# glucoschema.net
KiCad netlist of a schematic drawn in EAGLE
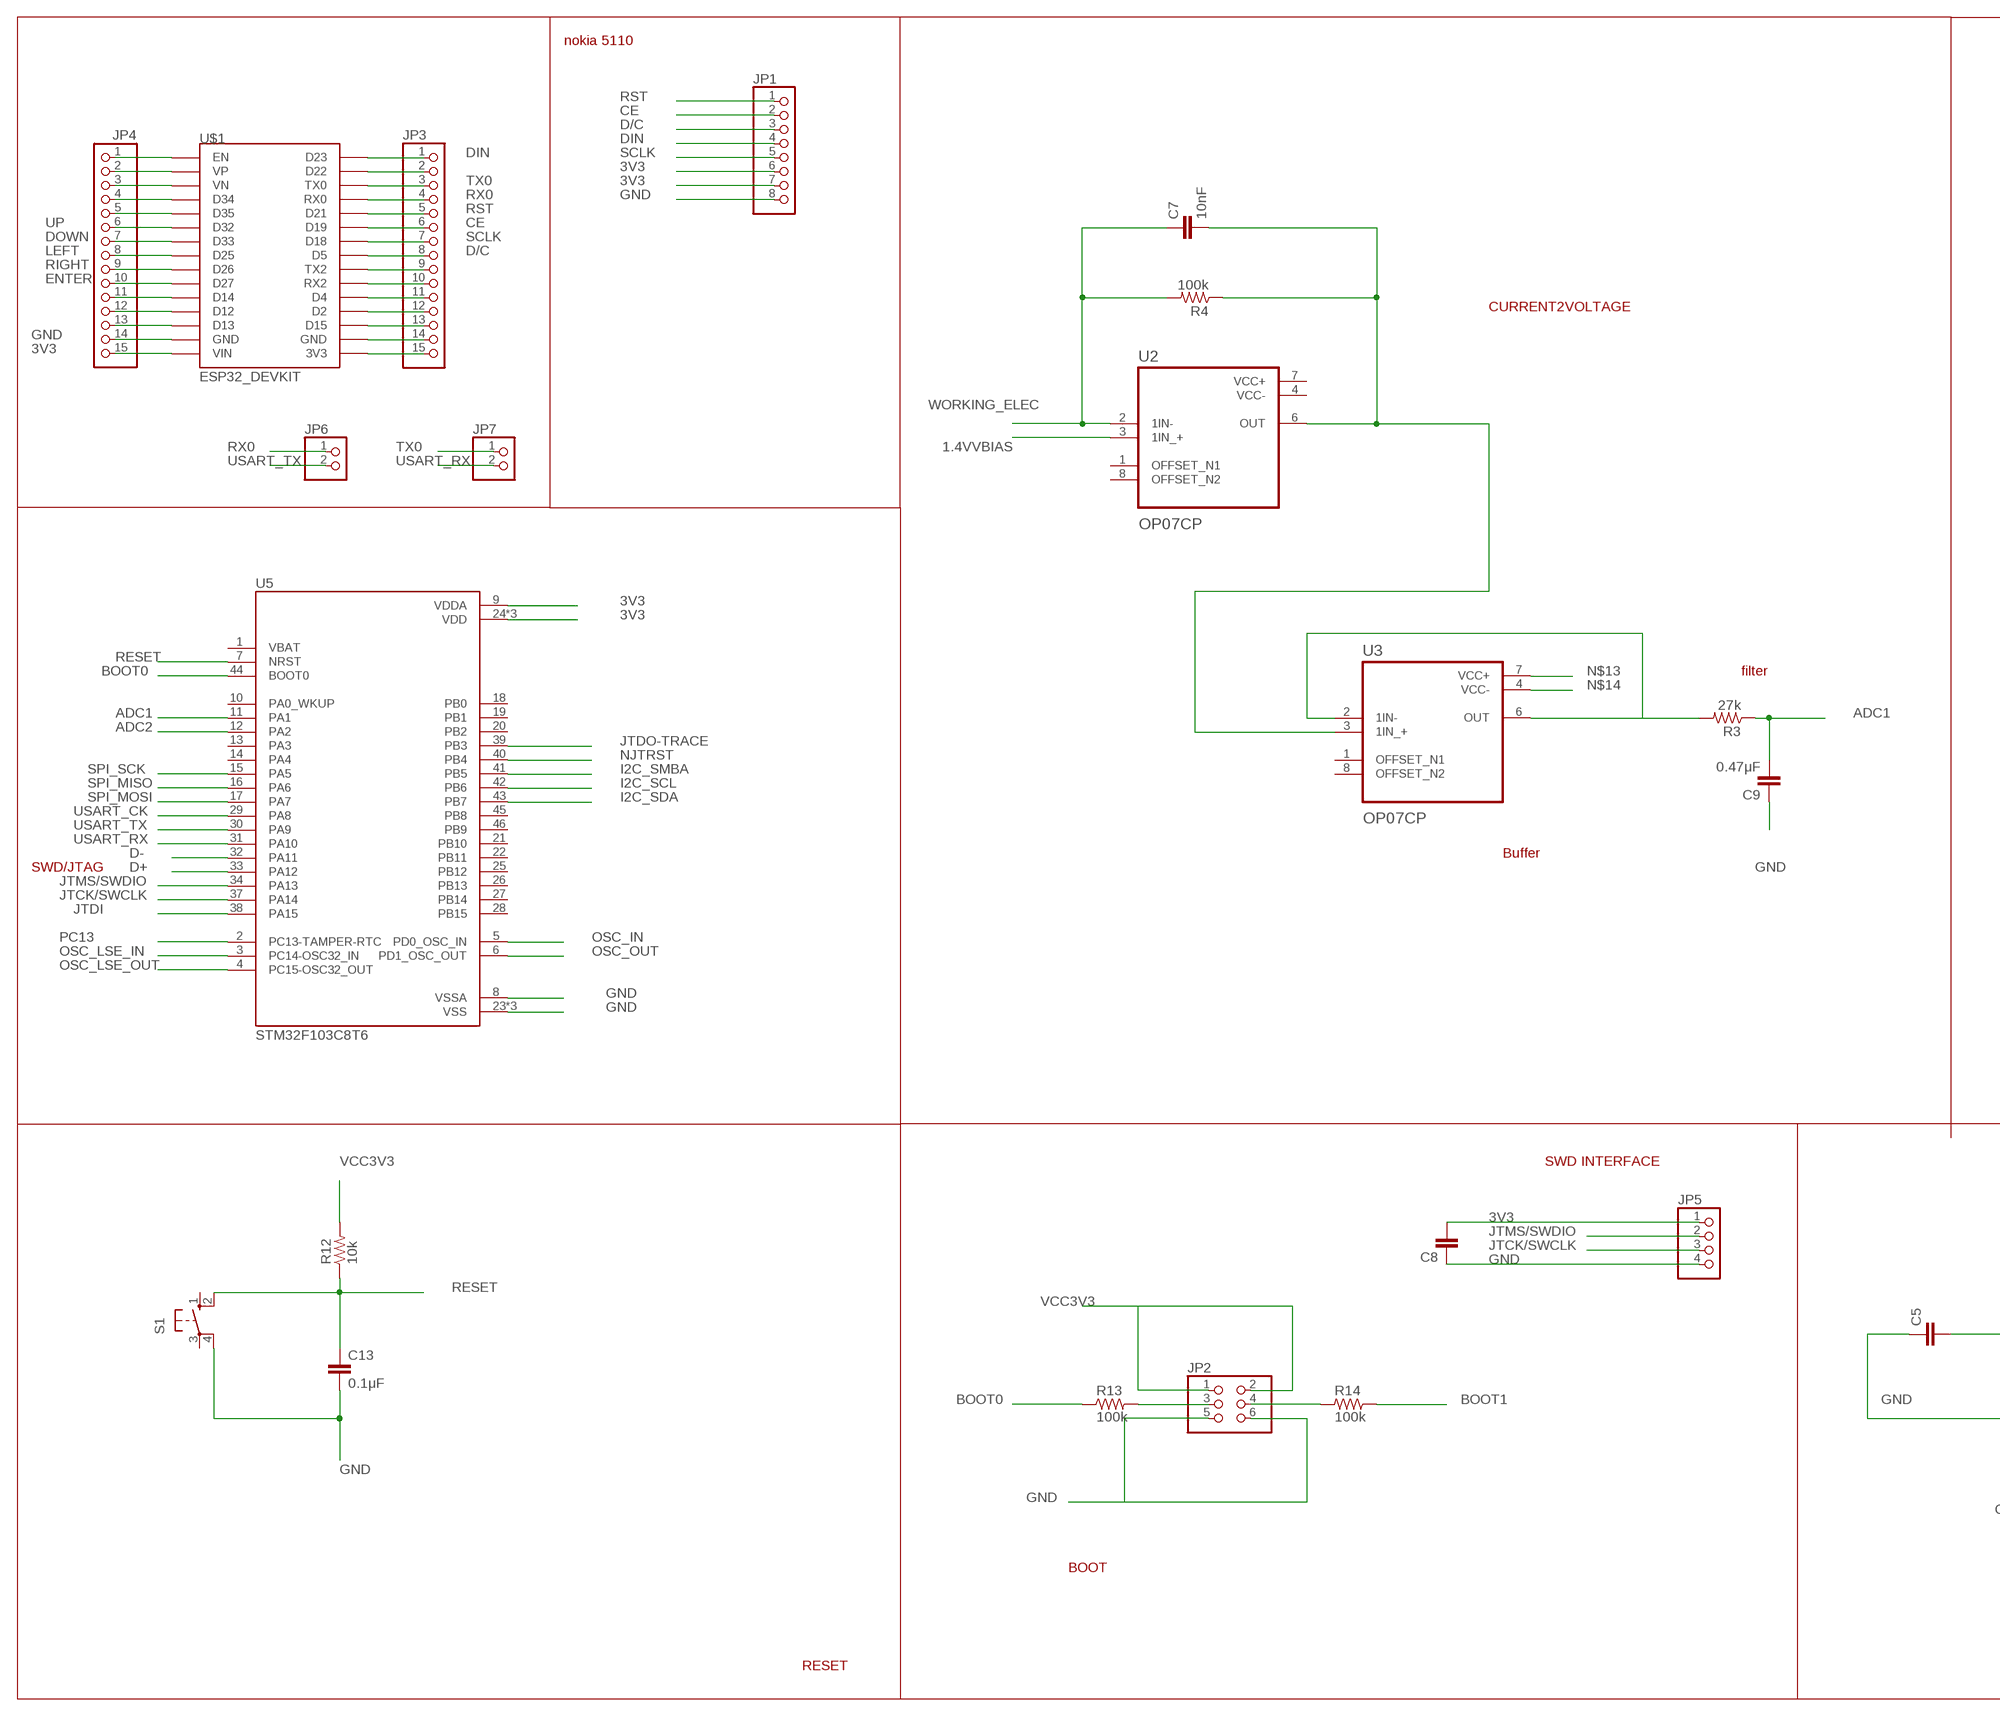
[diagram p0: schematic, sheet 1, part 1 of 2]
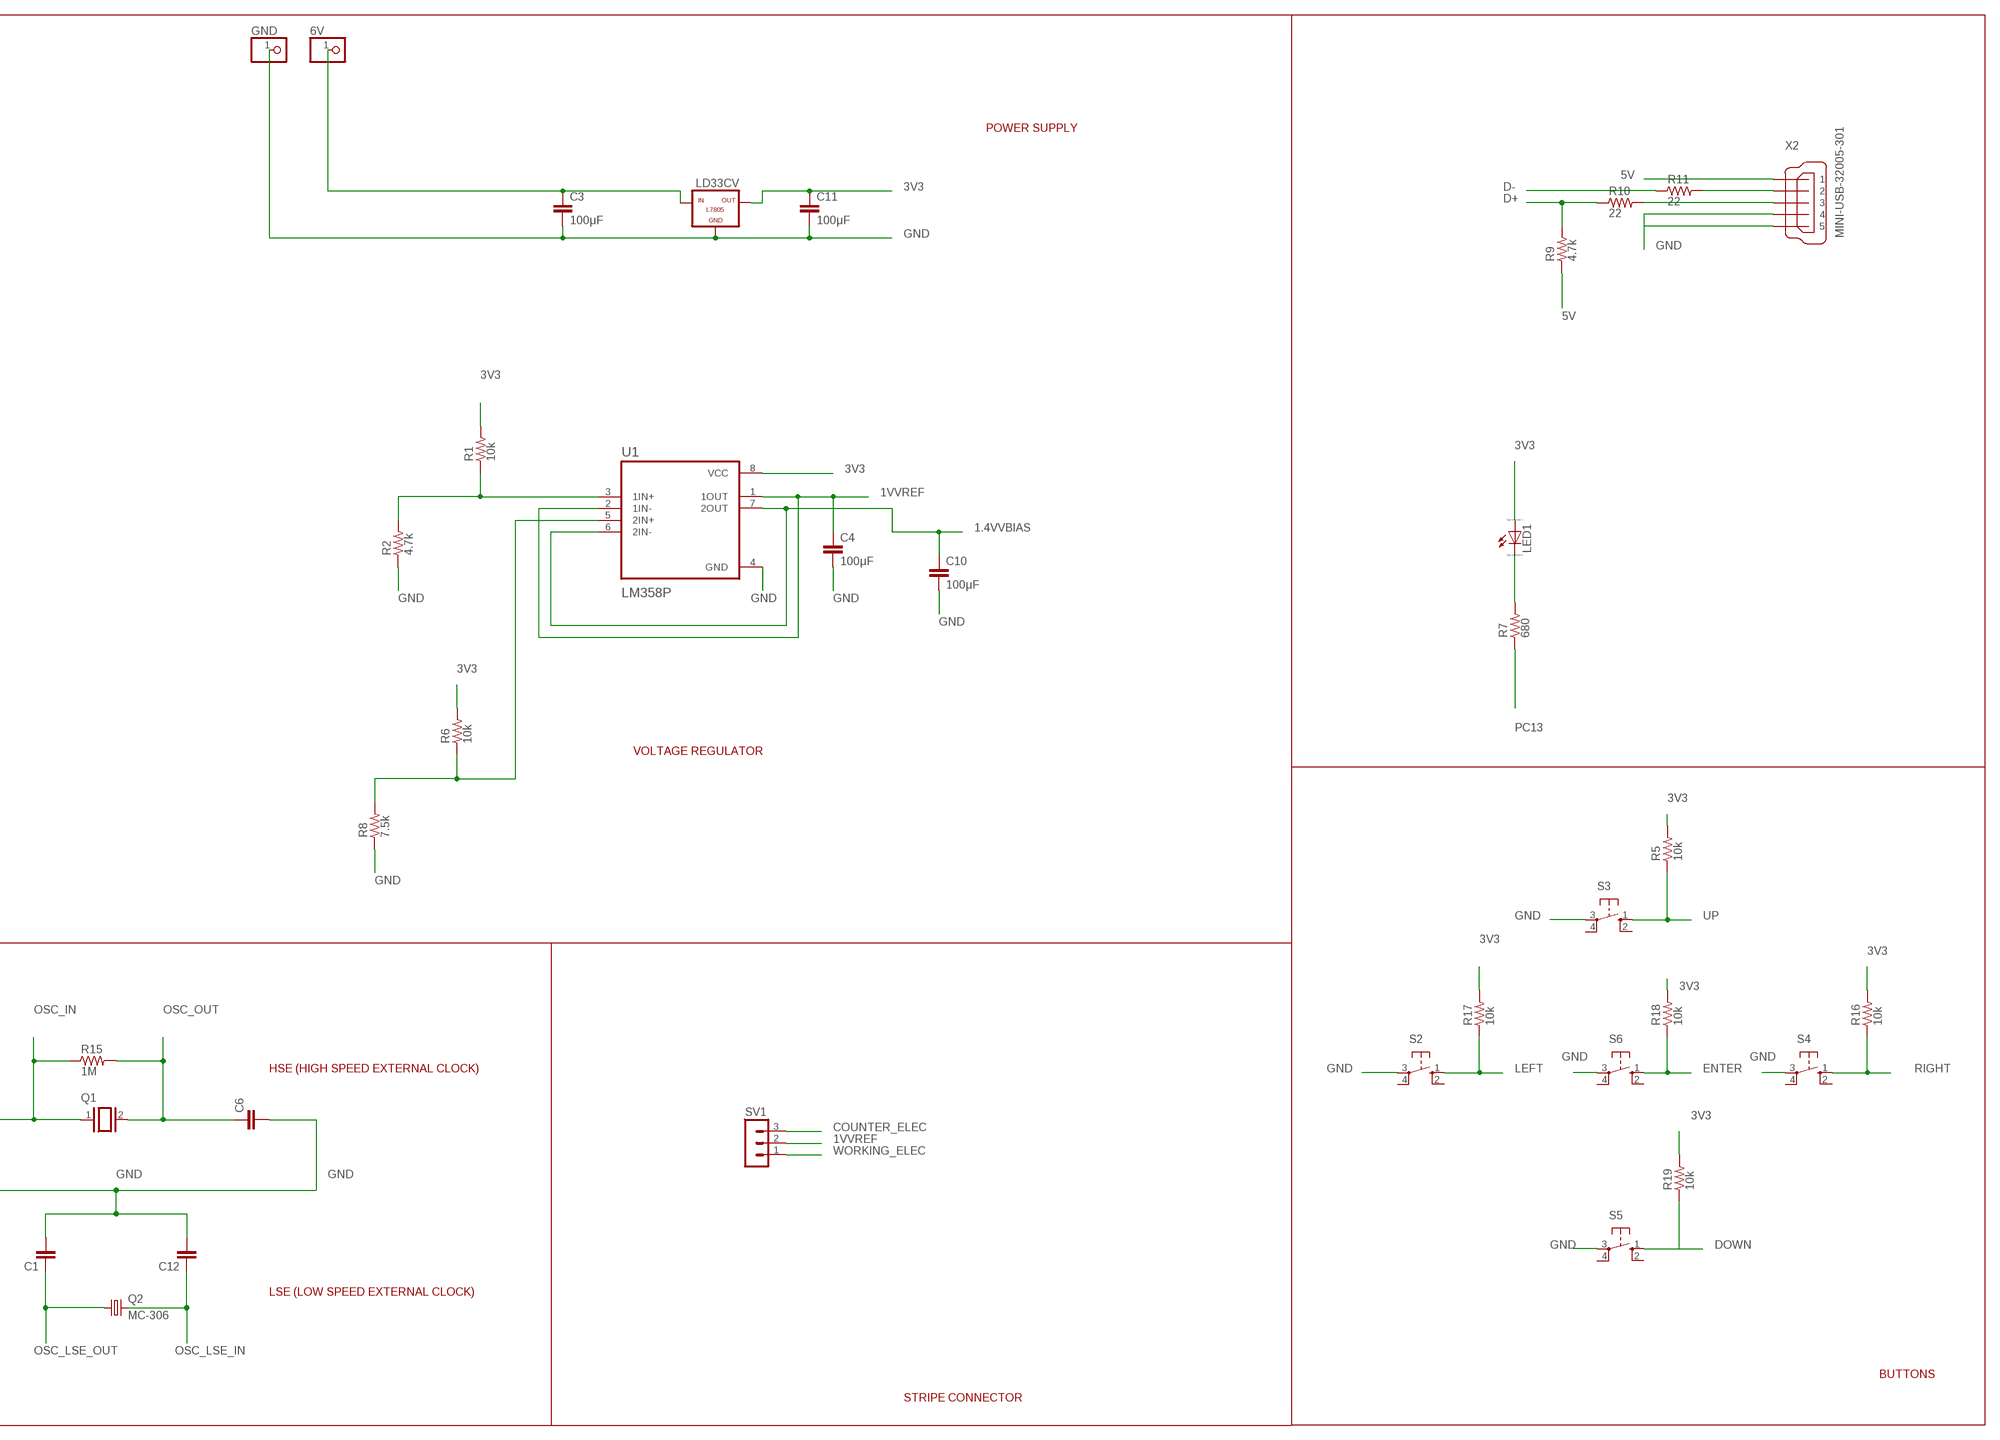
[diagram p1: schematic, sheet 1, part 2 of 2]

(export (version "E")
  (design (tool "Eeschema 10.0.6"))
  (components
    (comp (ref "6V")
      (value "PINHD-1X1")
      (footprint "eagle-import:1X01")
      (libsource (lib "eagle-import") (part "PINHD-1X1"))
    )
    (comp (ref "C1")
      (value "C2.5/4")
      (footprint "eagle-import:C2.5-4")
      (libsource (lib "eagle-import") (part "C2.5/4"))
    )
    (comp (ref "C3")
      (value "100μF")
      (footprint "eagle-import:C2.5-4")
      (libsource (lib "eagle-import") (part "C2.5/4"))
    )
    (comp (ref "C4")
      (value "100μF")
      (footprint "eagle-import:C2.5-4")
      (libsource (lib "eagle-import") (part "C2.5/4"))
    )
    (comp (ref "C5")
      (value "C2.5/4")
      (footprint "eagle-import:C2.5-4")
      (libsource (lib "eagle-import") (part "C2.5/4"))
    )
    (comp (ref "C6")
      (value "C2.5/4")
      (footprint "eagle-import:C2.5-4")
      (libsource (lib "eagle-import") (part "C2.5/4"))
    )
    (comp (ref "C7")
      (value "10nF")
      (footprint "eagle-import:C2.5-4")
      (libsource (lib "eagle-import") (part "C2.5/4"))
    )
    (comp (ref "C8")
      (value "C2.5/4")
      (footprint "eagle-import:C2.5-4")
      (libsource (lib "eagle-import") (part "C2.5/4"))
    )
    (comp (ref "C9")
      (value "0.47μF")
      (footprint "eagle-import:C2.5-4")
      (libsource (lib "eagle-import") (part "C2.5/4"))
    )
    (comp (ref "C10")
      (value "100μF")
      (footprint "eagle-import:C2.5-4")
      (libsource (lib "eagle-import") (part "C2.5/4"))
    )
    (comp (ref "C11")
      (value "100μF")
      (footprint "eagle-import:C2.5-4")
      (libsource (lib "eagle-import") (part "C2.5/4"))
    )
    (comp (ref "C12")
      (value "C2.5/4")
      (footprint "eagle-import:C2.5-4")
      (libsource (lib "eagle-import") (part "C2.5/4"))
    )
    (comp (ref "C13")
      (value "0.1μF")
      (footprint "eagle-import:C2.5-4")
      (libsource (lib "eagle-import") (part "C2.5/4"))
    )
    (comp (ref "GND")
      (value "PINHD-1X1")
      (footprint "eagle-import:1X01")
      (libsource (lib "eagle-import") (part "PINHD-1X1"))
    )
    (comp (ref "JP1")
      (value "PINHD-1X8")
      (footprint "eagle-import:1X08")
      (libsource (lib "eagle-import") (part "PINHD-1X8"))
    )
    (comp (ref "JP2")
      (value "PINHD-2X3")
      (footprint "eagle-import:2X03")
      (libsource (lib "eagle-import") (part "PINHD-2X3"))
    )
    (comp (ref "JP3")
      (value "PINHD-1X15")
      (footprint "eagle-import:1X15")
      (libsource (lib "eagle-import") (part "PINHD-1X15"))
    )
    (comp (ref "JP4")
      (value "PINHD-1X15")
      (footprint "eagle-import:1X15")
      (libsource (lib "eagle-import") (part "PINHD-1X15"))
    )
    (comp (ref "JP5")
      (value "PINHD-1X4")
      (footprint "eagle-import:1X04")
      (libsource (lib "eagle-import") (part "PINHD-1X4"))
    )
    (comp (ref "JP6")
      (value "PINHD-1X2")
      (footprint "eagle-import:1X02")
      (libsource (lib "eagle-import") (part "PINHD-1X2"))
    )
    (comp (ref "JP7")
      (value "PINHD-1X2")
      (footprint "eagle-import:1X02")
      (libsource (lib "eagle-import") (part "PINHD-1X2"))
    )
    (comp (ref "LD33CV")
      (value "-L7805")
      (footprint "eagle-import:L7805")
      (libsource (lib "eagle-import") (part "-L7805"))
    )
    (comp (ref "LED1")
      (value "LED_E")
      (footprint "eagle-import:LED_1206")
      (libsource (lib "eagle-import") (part "LED_E"))
    )
    (comp (ref "Q1")
      (value "XTAL/S")
      (footprint "eagle-import:QS")
      (libsource (lib "eagle-import") (part "XTAL/S"))
    )
    (comp (ref "Q2")
      (value "MC-306")
      (footprint "eagle-import:MC-306")
      (fields (field (name "MPN") "MC-306 60.0KHZ  100PPM ,12.5PF"))
      (libsource (lib "eagle-import") (part "MC-306"))
    )
    (comp (ref "R1")
      (value "10k")
      (footprint "eagle-import:R0805")
      (libsource (lib "eagle-import") (part "R_0805"))
    )
    (comp (ref "R2")
      (value "4.7k")
      (footprint "eagle-import:R0805")
      (libsource (lib "eagle-import") (part "R_0805"))
    )
    (comp (ref "R3")
      (value "27k")
      (footprint "eagle-import:R0805")
      (libsource (lib "eagle-import") (part "R_0805"))
    )
    (comp (ref "R4")
      (value "100k")
      (footprint "eagle-import:R0805")
      (libsource (lib "eagle-import") (part "R_0805"))
    )
    (comp (ref "R5")
      (value "10k")
      (footprint "eagle-import:R0805")
      (libsource (lib "eagle-import") (part "R_0805"))
    )
    (comp (ref "R6")
      (value "10k")
      (footprint "eagle-import:R0805")
      (libsource (lib "eagle-import") (part "R_0805"))
    )
    (comp (ref "R7")
      (value "680")
      (footprint "eagle-import:R0805")
      (libsource (lib "eagle-import") (part "R_0805"))
    )
    (comp (ref "R8")
      (value "7.5k")
      (footprint "eagle-import:R0805")
      (libsource (lib "eagle-import") (part "R_0805"))
    )
    (comp (ref "R9")
      (value "4.7k")
      (footprint "eagle-import:R0805")
      (libsource (lib "eagle-import") (part "R_0805"))
    )
    (comp (ref "R10")
      (value "22")
      (footprint "eagle-import:R0805")
      (libsource (lib "eagle-import") (part "R_0805"))
    )
    (comp (ref "R11")
      (value "22")
      (footprint "eagle-import:R0805")
      (libsource (lib "eagle-import") (part "R_0805"))
    )
    (comp (ref "R12")
      (value "10k")
      (footprint "eagle-import:R0805")
      (libsource (lib "eagle-import") (part "R_0805"))
    )
    (comp (ref "R13")
      (value "100k")
      (footprint "eagle-import:R0805")
      (libsource (lib "eagle-import") (part "R_0805"))
    )
    (comp (ref "R14")
      (value "100k")
      (footprint "eagle-import:R0805")
      (libsource (lib "eagle-import") (part "R_0805"))
    )
    (comp (ref "R15")
      (value "1M")
      (footprint "eagle-import:R0805")
      (libsource (lib "eagle-import") (part "R_0805"))
    )
    (comp (ref "R16")
      (value "10k")
      (footprint "eagle-import:R0805")
      (libsource (lib "eagle-import") (part "R_0805"))
    )
    (comp (ref "R17")
      (value "10k")
      (footprint "eagle-import:R0805")
      (libsource (lib "eagle-import") (part "R_0805"))
    )
    (comp (ref "R18")
      (value "10k")
      (footprint "eagle-import:R0805")
      (libsource (lib "eagle-import") (part "R_0805"))
    )
    (comp (ref "R19")
      (value "10k")
      (footprint "eagle-import:R0805")
      (libsource (lib "eagle-import") (part "R_0805"))
    )
    (comp (ref "S1")
      (value "10-XX")
      (footprint "eagle-import:B3F-10XX")
      (fields (field (name "MPN") "B3F-1000"))
      (libsource (lib "eagle-import") (part "10-XX"))
    )
    (comp (ref "S2")
      (value "10-XX")
      (footprint "eagle-import:B3F-10XX")
      (fields (field (name "MPN") "B3F-1000"))
      (libsource (lib "eagle-import") (part "10-XX"))
    )
    (comp (ref "S3")
      (value "10-XX")
      (footprint "eagle-import:B3F-10XX")
      (fields (field (name "MPN") "B3F-1000"))
      (libsource (lib "eagle-import") (part "10-XX"))
    )
    (comp (ref "S4")
      (value "10-XX")
      (footprint "eagle-import:B3F-10XX")
      (fields (field (name "MPN") "B3F-1000"))
      (libsource (lib "eagle-import") (part "10-XX"))
    )
    (comp (ref "S5")
      (value "10-XX")
      (footprint "eagle-import:B3F-10XX")
      (fields (field (name "MPN") "B3F-1000"))
      (libsource (lib "eagle-import") (part "10-XX"))
    )
    (comp (ref "S6")
      (value "10-XX")
      (footprint "eagle-import:B3F-10XX")
      (fields (field (name "MPN") "B3F-1000"))
      (libsource (lib "eagle-import") (part "10-XX"))
    )
    (comp (ref "SV1")
      (value "MA03-1")
      (footprint "eagle-import:MA03-1")
      (libsource (lib "eagle-import") (part "MA03-1"))
    )
    (comp (ref "U$1")
      (value "ESP32_DEVKIT")
      (footprint "eagle-import:ESP32_DEVKIT")
      (libsource (lib "eagle-import") (part "ESP32_DEVKIT"))
    )
    (comp (ref "U1")
      (value "LM358P")
      (footprint "eagle-import:DIP794W45P254L959H508Q8")
      (fields (field (name "MF") "Texas Instruments"))
      (libsource (lib "eagle-import") (part "LM358P"))
    )
    (comp (ref "U2")
      (value "OP07CP")
      (footprint "eagle-import:DIP794W45P254L959H508Q8")
      (fields (field (name "MF") "Texas Instruments"))
      (libsource (lib "eagle-import") (part "OP07CP"))
    )
    (comp (ref "U3")
      (value "OP07CP")
      (footprint "eagle-import:DIP794W45P254L959H508Q8")
      (fields (field (name "MF") "Texas Instruments"))
      (libsource (lib "eagle-import") (part "OP07CP"))
    )
    (comp (ref "U5")
      (value "STM32F103C8T6")
      (footprint "eagle-import:QFP50P900X900X160-48N")
      (fields (field (name "MF") "STMicroelectronics"))
      (libsource (lib "eagle-import") (part "STM32F103C8T6"))
    )
    (comp (ref "X2")
      (value "MINI-USB-32005-301")
      (footprint "eagle-import:32005-301")
      (libsource (lib "eagle-import") (part "MINI-USB-32005-301"))
    )
  )
  (nets
    (net (code "1") (name "/1.4VVBIAS") (class "Default")
      (node (ref "C10") (pin "1") (pinfunction "1_1") (pintype "passive"))
      (node (ref "U1") (pin "6") (pinfunction "2IN-_6") (pintype "input"))
      (node (ref "U1") (pin "7") (pinfunction "2OUT_7") (pintype "output"))
      (node (ref "U2") (pin "3") (pinfunction "1IN_+_3") (pintype "input"))
    )
    (net (code "2") (name "/1VVREF") (class "Default")
      (node (ref "C4") (pin "1") (pinfunction "1_1") (pintype "passive"))
      (node (ref "SV1") (pin "2") (pinfunction "2_2") (pintype "passive"))
      (node (ref "U1") (pin "1") (pinfunction "1OUT_1") (pintype "output"))
      (node (ref "U1") (pin "2") (pinfunction "1IN-_2") (pintype "input"))
    )
    (net (code "3") (name "/3V3") (class "Default")
      (node (ref "C11") (pin "1") (pinfunction "1_1") (pintype "passive"))
      (node (ref "C8") (pin "2") (pinfunction "2_2") (pintype "passive"))
      (node (ref "JP1") (pin "6") (pinfunction "6_6") (pintype "passive"))
      (node (ref "JP1") (pin "7") (pinfunction "7_7") (pintype "passive"))
      (node (ref "JP4") (pin "15") (pinfunction "15_15") (pintype "passive"))
      (node (ref "JP5") (pin "1") (pinfunction "1_1") (pintype "passive"))
      (node (ref "LD33CV") (pin "OUT") (pinfunction "OUT_OUT") (pintype "passive"))
      (node (ref "LED1") (pin "A") (pinfunction "A_A") (pintype "passive"))
      (node (ref "R1") (pin "2") (pinfunction "2_2") (pintype "passive"))
      (node (ref "R16") (pin "2") (pinfunction "2_2") (pintype "passive"))
      (node (ref "R17") (pin "2") (pinfunction "2_2") (pintype "passive"))
      (node (ref "R18") (pin "2") (pinfunction "2_2") (pintype "passive"))
      (node (ref "R19") (pin "2") (pinfunction "2_2") (pintype "passive"))
      (node (ref "R5") (pin "2") (pinfunction "2_2") (pintype "passive"))
      (node (ref "R6") (pin "2") (pinfunction "2_2") (pintype "passive"))
      (node (ref "U$1") (pin "VIN") (pinfunction "VIN_VIN") (pintype "bidirectional"))
      (node (ref "U1") (pin "8") (pinfunction "VCC_8") (pintype "power_in"))
      (node (ref "U5") (pin "24") (pinfunction "VDD_24") (pintype "power_in"))
      (node (ref "U5") (pin "36") (pinfunction "VDD_36") (pintype "power_in"))
      (node (ref "U5") (pin "48") (pinfunction "VDD_48") (pintype "power_in"))
      (node (ref "U5") (pin "9") (pinfunction "VDDA_9") (pintype "power_in"))
    )
    (net (code "4") (name "/5V") (class "Default")
      (node (ref "R9") (pin "1") (pinfunction "1_1") (pintype "passive"))
      (node (ref "X2") (pin "1") (pinfunction "1_1") (pintype "passive"))
    )
    (net (code "5") (name "/ADC1") (class "Default")
      (node (ref "C9") (pin "2") (pinfunction "2_2") (pintype "passive"))
      (node (ref "R3") (pin "1") (pinfunction "1_1") (pintype "passive"))
      (node (ref "U5") (pin "11") (pinfunction "PA1_11") (pintype "bidirectional"))
    )
    (net (code "6") (name "/ADC2") (class "Default")
      (node (ref "U5") (pin "12") (pinfunction "PA2_12") (pintype "bidirectional"))
    )
    (net (code "7") (name "/BOOT0") (class "Default")
      (node (ref "R13") (pin "1") (pinfunction "1_1") (pintype "passive"))
      (node (ref "U5") (pin "44") (pinfunction "BOOT0_44") (pintype "input"))
    )
    (net (code "8") (name "/BOOT1") (class "Default")
      (node (ref "R14") (pin "2") (pinfunction "2_2") (pintype "passive"))
    )
    (net (code "9") (name "/CE") (class "Default")
      (node (ref "JP1") (pin "2") (pinfunction "2_2") (pintype "passive"))
      (node (ref "JP3") (pin "6") (pinfunction "6_6") (pintype "passive"))
      (node (ref "U$1") (pin "D19") (pinfunction "D19_D19") (pintype "bidirectional"))
    )
    (net (code "10") (name "/COUNTER_ELEC") (class "Default")
      (node (ref "SV1") (pin "3") (pinfunction "3_3") (pintype "passive"))
    )
    (net (code "11") (name "/D+") (class "Default")
      (node (ref "R10") (pin "1") (pinfunction "1_1") (pintype "passive"))
      (node (ref "R9") (pin "2") (pinfunction "2_2") (pintype "passive"))
      (node (ref "U5") (pin "33") (pinfunction "PA12_33") (pintype "bidirectional"))
    )
    (net (code "12") (name "/D-") (class "Default")
      (node (ref "R11") (pin "1") (pinfunction "1_1") (pintype "passive"))
      (node (ref "U5") (pin "32") (pinfunction "PA11_32") (pintype "bidirectional"))
    )
    (net (code "13") (name "/DIN") (class "Default")
      (node (ref "JP1") (pin "4") (pinfunction "4_4") (pintype "passive"))
      (node (ref "JP3") (pin "1") (pinfunction "1_1") (pintype "passive"))
      (node (ref "U$1") (pin "D23") (pinfunction "D23_D23") (pintype "bidirectional"))
    )
    (net (code "14") (name "/DOWN") (class "Default")
      (node (ref "JP4") (pin "7") (pinfunction "7_7") (pintype "passive"))
      (node (ref "R19") (pin "1") (pinfunction "1_1") (pintype "passive"))
      (node (ref "S5") (pin "1") (pinfunction "S_1") (pintype "passive"))
      (node (ref "U$1") (pin "D33") (pinfunction "D33_D33") (pintype "bidirectional"))
    )
    (net (code "15") (name "/D{slash}C") (class "Default")
      (node (ref "JP1") (pin "3") (pinfunction "3_3") (pintype "passive"))
      (node (ref "JP3") (pin "8") (pinfunction "8_8") (pintype "passive"))
      (node (ref "U$1") (pin "D5") (pinfunction "D5_D5") (pintype "bidirectional"))
    )
    (net (code "16") (name "/ENTER") (class "Default")
      (node (ref "JP4") (pin "10") (pinfunction "10_10") (pintype "passive"))
      (node (ref "R18") (pin "1") (pinfunction "1_1") (pintype "passive"))
      (node (ref "S6") (pin "1") (pinfunction "S_1") (pintype "passive"))
      (node (ref "U$1") (pin "D27") (pinfunction "D27_D27") (pintype "bidirectional"))
    )
    (net (code "17") (name "/GND") (class "Default")
      (node (ref "C1") (pin "2") (pinfunction "2_2") (pintype "passive"))
      (node (ref "C10") (pin "2") (pinfunction "2_2") (pintype "passive"))
      (node (ref "C11") (pin "2") (pinfunction "2_2") (pintype "passive"))
      (node (ref "C12") (pin "2") (pinfunction "2_2") (pintype "passive"))
      (node (ref "C13") (pin "2") (pinfunction "2_2") (pintype "passive"))
      (node (ref "C3") (pin "2") (pinfunction "2_2") (pintype "passive"))
      (node (ref "C4") (pin "2") (pinfunction "2_2") (pintype "passive"))
      (node (ref "C5") (pin "1") (pinfunction "1_1") (pintype "passive"))
      (node (ref "C6") (pin "2") (pinfunction "2_2") (pintype "passive"))
      (node (ref "C8") (pin "1") (pinfunction "1_1") (pintype "passive"))
      (node (ref "C9") (pin "1") (pinfunction "1_1") (pintype "passive"))
      (node (ref "GND") (pin "1") (pinfunction "1_1") (pintype "passive"))
      (node (ref "JP1") (pin "8") (pinfunction "8_8") (pintype "passive"))
      (node (ref "JP2") (pin "6") (pinfunction "6_6") (pintype "passive"))
      (node (ref "JP4") (pin "14") (pinfunction "14_14") (pintype "passive"))
      (node (ref "JP5") (pin "4") (pinfunction "4_4") (pintype "passive"))
      (node (ref "LD33CV") (pin "GND") (pinfunction "GND_GND") (pintype "input"))
      (node (ref "R2") (pin "1") (pinfunction "1_1") (pintype "passive"))
      (node (ref "R8") (pin "1") (pinfunction "1_1") (pintype "passive"))
      (node (ref "S1") (pin "4") (pinfunction "P1_4") (pintype "passive"))
      (node (ref "S2") (pin "3") (pinfunction "P_3") (pintype "passive"))
      (node (ref "S3") (pin "3") (pinfunction "P_3") (pintype "passive"))
      (node (ref "S4") (pin "3") (pinfunction "P_3") (pintype "passive"))
      (node (ref "S5") (pin "3") (pinfunction "P_3") (pintype "passive"))
      (node (ref "S6") (pin "3") (pinfunction "P_3") (pintype "passive"))
      (node (ref "U$1") (pin "GND@1") (pinfunction "GND_GND@1") (pintype "bidirectional"))
      (node (ref "U1") (pin "4") (pinfunction "GND_4") (pintype "power_in"))
      (node (ref "U5") (pin "23") (pinfunction "VSS_23") (pintype "power_in"))
      (node (ref "U5") (pin "35") (pinfunction "VSS_35") (pintype "power_in"))
      (node (ref "U5") (pin "47") (pinfunction "VSS_47") (pintype "power_in"))
      (node (ref "U5") (pin "8") (pinfunction "VSSA_8") (pintype "power_in"))
      (node (ref "X2") (pin "4") (pinfunction "4_4") (pintype "passive"))
    )
    (net (code "18") (name "/I2C_SCL") (class "Default")
      (node (ref "U5") (pin "42") (pinfunction "PB6_42") (pintype "bidirectional"))
    )
    (net (code "19") (name "/I2C_SDA") (class "Default")
      (node (ref "U5") (pin "43") (pinfunction "PB7_43") (pintype "bidirectional"))
    )
    (net (code "20") (name "/I2C_SMBA") (class "Default")
      (node (ref "U5") (pin "41") (pinfunction "PB5_41") (pintype "bidirectional"))
    )
    (net (code "21") (name "/JTCK{slash}SWCLK") (class "Default")
      (node (ref "JP5") (pin "3") (pinfunction "3_3") (pintype "passive"))
      (node (ref "U5") (pin "37") (pinfunction "PA14_37") (pintype "bidirectional"))
    )
    (net (code "22") (name "/JTDI") (class "Default")
      (node (ref "U5") (pin "38") (pinfunction "PA15_38") (pintype "bidirectional"))
    )
    (net (code "23") (name "/JTDO-TRACE") (class "Default")
      (node (ref "U5") (pin "39") (pinfunction "PB3_39") (pintype "bidirectional"))
    )
    (net (code "24") (name "/JTMS{slash}SWDIO") (class "Default")
      (node (ref "JP5") (pin "2") (pinfunction "2_2") (pintype "passive"))
      (node (ref "U5") (pin "34") (pinfunction "PA13_34") (pintype "bidirectional"))
    )
    (net (code "25") (name "/LEFT") (class "Default")
      (node (ref "JP4") (pin "8") (pinfunction "8_8") (pintype "passive"))
      (node (ref "R17") (pin "1") (pinfunction "1_1") (pintype "passive"))
      (node (ref "S2") (pin "1") (pinfunction "S_1") (pintype "passive"))
      (node (ref "U$1") (pin "D25") (pinfunction "D25_D25") (pintype "bidirectional"))
    )
    (net (code "26") (name "/N$13") (class "Default")
      (node (ref "U3") (pin "7") (pinfunction "VCC+_7") (pintype "power_in"))
    )
    (net (code "27") (name "/N$14") (class "Default")
      (node (ref "U3") (pin "4") (pinfunction "VCC-_4") (pintype "power_in"))
    )
    (net (code "28") (name "/NJTRST") (class "Default")
      (node (ref "U5") (pin "40") (pinfunction "PB4_40") (pintype "bidirectional"))
    )
    (net (code "29") (name "/OSC_IN") (class "Default")
      (node (ref "C5") (pin "2") (pinfunction "2_2") (pintype "passive"))
      (node (ref "Q1") (pin "1") (pinfunction "1_1") (pintype "passive"))
      (node (ref "R15") (pin "1") (pinfunction "1_1") (pintype "passive"))
      (node (ref "U5") (pin "5") (pinfunction "PD0_OSC_IN_5") (pintype "bidirectional"))
    )
    (net (code "30") (name "/OSC_LSE_IN") (class "Default")
      (node (ref "C12") (pin "1") (pinfunction "1_1") (pintype "passive"))
      (node (ref "Q2") (pin "4") (pinfunction "2_4") (pintype "passive"))
      (node (ref "U5") (pin "3") (pinfunction "PC14-OSC32_IN_3") (pintype "bidirectional"))
    )
    (net (code "31") (name "/OSC_LSE_OUT") (class "Default")
      (node (ref "C1") (pin "1") (pinfunction "1_1") (pintype "passive"))
      (node (ref "Q2") (pin "1") (pinfunction "1_1") (pintype "passive"))
      (node (ref "U5") (pin "4") (pinfunction "PC15-OSC32_OUT_4") (pintype "bidirectional"))
    )
    (net (code "32") (name "/OSC_OUT") (class "Default")
      (node (ref "C6") (pin "1") (pinfunction "1_1") (pintype "passive"))
      (node (ref "Q1") (pin "2") (pinfunction "2_2") (pintype "passive"))
      (node (ref "R15") (pin "2") (pinfunction "2_2") (pintype "passive"))
      (node (ref "U5") (pin "6") (pinfunction "PD1_OSC_OUT_6") (pintype "bidirectional"))
    )
    (net (code "33") (name "/PC13") (class "Default")
      (node (ref "R7") (pin "1") (pinfunction "1_1") (pintype "passive"))
      (node (ref "U5") (pin "2") (pinfunction "PC13-TAMPER-RTC_2") (pintype "bidirectional"))
    )
    (net (code "34") (name "/RESET") (class "Default")
      (node (ref "C13") (pin "1") (pinfunction "1_1") (pintype "passive"))
      (node (ref "R12") (pin "1") (pinfunction "1_1") (pintype "passive"))
      (node (ref "S1") (pin "2") (pinfunction "S1_2") (pintype "passive"))
      (node (ref "U5") (pin "7") (pinfunction "NRST_7") (pintype "input"))
    )
    (net (code "35") (name "/RIGHT") (class "Default")
      (node (ref "JP4") (pin "9") (pinfunction "9_9") (pintype "passive"))
      (node (ref "R16") (pin "1") (pinfunction "1_1") (pintype "passive"))
      (node (ref "S4") (pin "1") (pinfunction "S_1") (pintype "passive"))
      (node (ref "U$1") (pin "D26") (pinfunction "D26_D26") (pintype "bidirectional"))
    )
    (net (code "36") (name "/RST") (class "Default")
      (node (ref "JP1") (pin "1") (pinfunction "1_1") (pintype "passive"))
      (node (ref "JP3") (pin "5") (pinfunction "5_5") (pintype "passive"))
      (node (ref "U$1") (pin "D21") (pinfunction "D21_D21") (pintype "bidirectional"))
    )
    (net (code "37") (name "/RX0") (class "Default")
      (node (ref "JP3") (pin "4") (pinfunction "4_4") (pintype "passive"))
      (node (ref "JP6") (pin "1") (pinfunction "1_1") (pintype "passive"))
      (node (ref "U$1") (pin "RX0") (pinfunction "RX0_RX0") (pintype "bidirectional"))
    )
    (net (code "38") (name "/SCLK") (class "Default")
      (node (ref "JP1") (pin "5") (pinfunction "5_5") (pintype "passive"))
      (node (ref "JP3") (pin "7") (pinfunction "7_7") (pintype "passive"))
      (node (ref "U$1") (pin "D18") (pinfunction "D18_D18") (pintype "bidirectional"))
    )
    (net (code "39") (name "/SPI_MISO") (class "Default")
      (node (ref "U5") (pin "16") (pinfunction "PA6_16") (pintype "bidirectional"))
    )
    (net (code "40") (name "/SPI_MOSI") (class "Default")
      (node (ref "U5") (pin "17") (pinfunction "PA7_17") (pintype "bidirectional"))
    )
    (net (code "41") (name "/SPI_SCK") (class "Default")
      (node (ref "U5") (pin "15") (pinfunction "PA5_15") (pintype "bidirectional"))
    )
    (net (code "42") (name "/TX0") (class "Default")
      (node (ref "JP3") (pin "3") (pinfunction "3_3") (pintype "passive"))
      (node (ref "JP7") (pin "1") (pinfunction "1_1") (pintype "passive"))
      (node (ref "U$1") (pin "TX0") (pinfunction "TX0_TX0") (pintype "bidirectional"))
    )
    (net (code "43") (name "/UP") (class "Default")
      (node (ref "JP4") (pin "6") (pinfunction "6_6") (pintype "passive"))
      (node (ref "R5") (pin "1") (pinfunction "1_1") (pintype "passive"))
      (node (ref "S3") (pin "1") (pinfunction "S_1") (pintype "passive"))
      (node (ref "U$1") (pin "D32") (pinfunction "D32_D32") (pintype "bidirectional"))
    )
    (net (code "44") (name "/USART_CK") (class "Default")
      (node (ref "U5") (pin "29") (pinfunction "PA8_29") (pintype "bidirectional"))
    )
    (net (code "45") (name "/USART_RX") (class "Default")
      (node (ref "JP7") (pin "2") (pinfunction "2_2") (pintype "passive"))
      (node (ref "U5") (pin "31") (pinfunction "PA10_31") (pintype "bidirectional"))
    )
    (net (code "46") (name "/USART_TX") (class "Default")
      (node (ref "JP6") (pin "2") (pinfunction "2_2") (pintype "passive"))
      (node (ref "U5") (pin "30") (pinfunction "PA9_30") (pintype "bidirectional"))
    )
    (net (code "47") (name "/VCC+") (class "Default")
      (node (ref "U2") (pin "7") (pinfunction "VCC+_7") (pintype "power_in"))
    )
    (net (code "48") (name "/VCC-") (class "Default")
      (node (ref "U2") (pin "4") (pinfunction "VCC-_4") (pintype "power_in"))
    )
    (net (code "49") (name "/VCC3V3") (class "Default")
      (node (ref "JP2") (pin "2") (pinfunction "2_2") (pintype "passive"))
      (node (ref "R12") (pin "2") (pinfunction "2_2") (pintype "passive"))
    )
    (net (code "50") (name "/WORKING_ELEC") (class "Default")
      (node (ref "C7") (pin "1") (pinfunction "1_1") (pintype "passive"))
      (node (ref "R4") (pin "2") (pinfunction "2_2") (pintype "passive"))
      (node (ref "SV1") (pin "1") (pinfunction "1_1") (pintype "passive"))
      (node (ref "U2") (pin "2") (pinfunction "1IN-_2") (pintype "input"))
    )
    (net (code "51") (name "Net-(6V-Pad1)") (class "Default")
      (node (ref "6V") (pin "1") (pinfunction "1_1") (pintype "passive"))
      (node (ref "C3") (pin "1") (pinfunction "1_1") (pintype "passive"))
      (node (ref "LD33CV") (pin "IN") (pinfunction "IN_IN") (pintype "input"))
    )
    (net (code "52") (name "Net-(JP2-Pad3)") (class "Default")
      (node (ref "JP2") (pin "3") (pinfunction "3_3") (pintype "passive"))
      (node (ref "R13") (pin "2") (pinfunction "2_2") (pintype "passive"))
    )
    (net (code "53") (name "Net-(JP2-Pad4)") (class "Default")
      (node (ref "JP2") (pin "4") (pinfunction "4_4") (pintype "passive"))
      (node (ref "R14") (pin "1") (pinfunction "1_1") (pintype "passive"))
    )
    (net (code "54") (name "Net-(JP3-Pad2)") (class "Default")
      (node (ref "JP3") (pin "2") (pinfunction "2_2") (pintype "passive"))
      (node (ref "U$1") (pin "D22") (pinfunction "D22_D22") (pintype "bidirectional"))
    )
    (net (code "55") (name "Net-(JP3-Pad9)") (class "Default")
      (node (ref "JP3") (pin "9") (pinfunction "9_9") (pintype "passive"))
      (node (ref "U$1") (pin "TX2") (pinfunction "TX2_TX2") (pintype "bidirectional"))
    )
    (net (code "56") (name "Net-(JP3-Pad10)") (class "Default")
      (node (ref "JP3") (pin "10") (pinfunction "10_10") (pintype "passive"))
      (node (ref "U$1") (pin "RX2") (pinfunction "RX2_RX2") (pintype "bidirectional"))
    )
    (net (code "57") (name "Net-(JP3-Pad11)") (class "Default")
      (node (ref "JP3") (pin "11") (pinfunction "11_11") (pintype "passive"))
      (node (ref "U$1") (pin "D4") (pinfunction "D4_D4") (pintype "bidirectional"))
    )
    (net (code "58") (name "Net-(JP3-Pad12)") (class "Default")
      (node (ref "JP3") (pin "12") (pinfunction "12_12") (pintype "passive"))
      (node (ref "U$1") (pin "D2") (pinfunction "D2_D2") (pintype "bidirectional"))
    )
    (net (code "59") (name "Net-(JP3-Pad13)") (class "Default")
      (node (ref "JP3") (pin "13") (pinfunction "13_13") (pintype "passive"))
      (node (ref "U$1") (pin "D15") (pinfunction "D15_D15") (pintype "bidirectional"))
    )
    (net (code "60") (name "Net-(JP3-Pad14)") (class "Default")
      (node (ref "JP3") (pin "14") (pinfunction "14_14") (pintype "passive"))
      (node (ref "U$1") (pin "GND@2") (pinfunction "GND_GND@2") (pintype "bidirectional"))
    )
    (net (code "61") (name "Net-(JP3-Pad15)") (class "Default")
      (node (ref "JP3") (pin "15") (pinfunction "15_15") (pintype "passive"))
      (node (ref "U$1") (pin "3V3") (pinfunction "3V3_3V3") (pintype "bidirectional"))
    )
    (net (code "62") (name "Net-(JP4-Pad1)") (class "Default")
      (node (ref "JP4") (pin "1") (pinfunction "1_1") (pintype "passive"))
      (node (ref "U$1") (pin "EN") (pinfunction "EN_EN") (pintype "bidirectional"))
    )
    (net (code "63") (name "Net-(JP4-Pad2)") (class "Default")
      (node (ref "JP4") (pin "2") (pinfunction "2_2") (pintype "passive"))
      (node (ref "U$1") (pin "VP") (pinfunction "VP_VP") (pintype "bidirectional"))
    )
    (net (code "64") (name "Net-(JP4-Pad3)") (class "Default")
      (node (ref "JP4") (pin "3") (pinfunction "3_3") (pintype "passive"))
      (node (ref "U$1") (pin "VN") (pinfunction "VN_VN") (pintype "bidirectional"))
    )
    (net (code "65") (name "Net-(JP4-Pad4)") (class "Default")
      (node (ref "JP4") (pin "4") (pinfunction "4_4") (pintype "passive"))
      (node (ref "U$1") (pin "D34") (pinfunction "D34_D34") (pintype "bidirectional"))
    )
    (net (code "66") (name "Net-(JP4-Pad5)") (class "Default")
      (node (ref "JP4") (pin "5") (pinfunction "5_5") (pintype "passive"))
      (node (ref "U$1") (pin "D35") (pinfunction "D35_D35") (pintype "bidirectional"))
    )
    (net (code "67") (name "Net-(JP4-Pad11)") (class "Default")
      (node (ref "JP4") (pin "11") (pinfunction "11_11") (pintype "passive"))
      (node (ref "U$1") (pin "D14") (pinfunction "D14_D14") (pintype "bidirectional"))
    )
    (net (code "68") (name "Net-(JP4-Pad12)") (class "Default")
      (node (ref "JP4") (pin "12") (pinfunction "12_12") (pintype "passive"))
      (node (ref "U$1") (pin "D12") (pinfunction "D12_D12") (pintype "bidirectional"))
    )
    (net (code "69") (name "Net-(JP4-Pad13)") (class "Default")
      (node (ref "JP4") (pin "13") (pinfunction "13_13") (pintype "passive"))
      (node (ref "U$1") (pin "D13") (pinfunction "D13_D13") (pintype "bidirectional"))
    )
    (net (code "70") (name "Net-(LED1-PadC)") (class "Default")
      (node (ref "LED1") (pin "C") (pinfunction "C_C") (pintype "passive"))
      (node (ref "R7") (pin "2") (pinfunction "2_2") (pintype "passive"))
    )
    (net (code "71") (name "Net-(R10-Pad2)") (class "Default")
      (node (ref "R10") (pin "2") (pinfunction "2_2") (pintype "passive"))
      (node (ref "X2") (pin "3") (pinfunction "3_3") (pintype "passive"))
    )
    (net (code "72") (name "Net-(R11-Pad2)") (class "Default")
      (node (ref "R11") (pin "2") (pinfunction "2_2") (pintype "passive"))
      (node (ref "X2") (pin "2") (pinfunction "2_2") (pintype "passive"))
    )
    (net (code "73") (name "Net-(U1-1IN+)") (class "Default")
      (node (ref "R1") (pin "1") (pinfunction "1_1") (pintype "passive"))
      (node (ref "R2") (pin "2") (pinfunction "2_2") (pintype "passive"))
      (node (ref "U1") (pin "3") (pinfunction "1IN+_3") (pintype "input"))
    )
    (net (code "74") (name "Net-(U1-2IN+)") (class "Default")
      (node (ref "R6") (pin "1") (pinfunction "1_1") (pintype "passive"))
      (node (ref "R8") (pin "2") (pinfunction "2_2") (pintype "passive"))
      (node (ref "U1") (pin "5") (pinfunction "2IN+_5") (pintype "input"))
    )
    (net (code "75") (name "Net-(U2-OUT)") (class "Default")
      (node (ref "C7") (pin "2") (pinfunction "2_2") (pintype "passive"))
      (node (ref "R4") (pin "1") (pinfunction "1_1") (pintype "passive"))
      (node (ref "U2") (pin "6") (pinfunction "OUT_6") (pintype "output"))
      (node (ref "U3") (pin "3") (pinfunction "1IN_+_3") (pintype "input"))
    )
    (net (code "76") (name "Net-(U3-1IN-)") (class "Default")
      (node (ref "R3") (pin "2") (pinfunction "2_2") (pintype "passive"))
      (node (ref "U3") (pin "2") (pinfunction "1IN-_2") (pintype "input"))
      (node (ref "U3") (pin "6") (pinfunction "OUT_6") (pintype "output"))
    )
    (net (code "77") (name "unconnected-(JP2-Pad1)") (class "Default")
      (node (ref "JP2") (pin "1") (pinfunction "1_1") (pintype "passive"))
    )
    (net (code "78") (name "unconnected-(JP2-Pad5)") (class "Default")
      (node (ref "JP2") (pin "5") (pinfunction "5_5") (pintype "passive"))
    )
    (net (code "79") (name "unconnected-(S1-P-Pad3)") (class "Default")
      (node (ref "S1") (pin "3") (pinfunction "P_3") (pintype "passive"))
    )
    (net (code "80") (name "unconnected-(S1-S-Pad1)") (class "Default")
      (node (ref "S1") (pin "1") (pinfunction "S_1") (pintype "passive"))
    )
    (net (code "81") (name "unconnected-(S2-P1-Pad4)") (class "Default")
      (node (ref "S2") (pin "4") (pinfunction "P1_4") (pintype "passive"))
    )
    (net (code "82") (name "unconnected-(S2-S1-Pad2)") (class "Default")
      (node (ref "S2") (pin "2") (pinfunction "S1_2") (pintype "passive"))
    )
    (net (code "83") (name "unconnected-(S3-P1-Pad4)") (class "Default")
      (node (ref "S3") (pin "4") (pinfunction "P1_4") (pintype "passive"))
    )
    (net (code "84") (name "unconnected-(S3-S1-Pad2)") (class "Default")
      (node (ref "S3") (pin "2") (pinfunction "S1_2") (pintype "passive"))
    )
    (net (code "85") (name "unconnected-(S4-P1-Pad4)") (class "Default")
      (node (ref "S4") (pin "4") (pinfunction "P1_4") (pintype "passive"))
    )
    (net (code "86") (name "unconnected-(S4-S1-Pad2)") (class "Default")
      (node (ref "S4") (pin "2") (pinfunction "S1_2") (pintype "passive"))
    )
    (net (code "87") (name "unconnected-(S5-P1-Pad4)") (class "Default")
      (node (ref "S5") (pin "4") (pinfunction "P1_4") (pintype "passive"))
    )
    (net (code "88") (name "unconnected-(S5-S1-Pad2)") (class "Default")
      (node (ref "S5") (pin "2") (pinfunction "S1_2") (pintype "passive"))
    )
    (net (code "89") (name "unconnected-(S6-P1-Pad4)") (class "Default")
      (node (ref "S6") (pin "4") (pinfunction "P1_4") (pintype "passive"))
    )
    (net (code "90") (name "unconnected-(S6-S1-Pad2)") (class "Default")
      (node (ref "S6") (pin "2") (pinfunction "S1_2") (pintype "passive"))
    )
    (net (code "91") (name "unconnected-(U2-OFFSET_N1-Pad1)") (class "Default")
      (node (ref "U2") (pin "1") (pinfunction "OFFSET_N1_1") (pintype "bidirectional"))
    )
    (net (code "92") (name "unconnected-(U2-OFFSET_N2-Pad8)") (class "Default")
      (node (ref "U2") (pin "8") (pinfunction "OFFSET_N2_8") (pintype "bidirectional"))
    )
    (net (code "93") (name "unconnected-(U3-OFFSET_N1-Pad1)") (class "Default")
      (node (ref "U3") (pin "1") (pinfunction "OFFSET_N1_1") (pintype "bidirectional"))
    )
    (net (code "94") (name "unconnected-(U3-OFFSET_N2-Pad8)") (class "Default")
      (node (ref "U3") (pin "8") (pinfunction "OFFSET_N2_8") (pintype "bidirectional"))
    )
    (net (code "95") (name "unconnected-(U5-PA0_WKUP-Pad10)") (class "Default")
      (node (ref "U5") (pin "10") (pinfunction "PA0_WKUP_10") (pintype "bidirectional"))
    )
    (net (code "96") (name "unconnected-(U5-PA3-Pad13)") (class "Default")
      (node (ref "U5") (pin "13") (pinfunction "PA3_13") (pintype "bidirectional"))
    )
    (net (code "97") (name "unconnected-(U5-PA4-Pad14)") (class "Default")
      (node (ref "U5") (pin "14") (pinfunction "PA4_14") (pintype "bidirectional"))
    )
    (net (code "98") (name "unconnected-(U5-PB0-Pad18)") (class "Default")
      (node (ref "U5") (pin "18") (pinfunction "PB0_18") (pintype "bidirectional"))
    )
    (net (code "99") (name "unconnected-(U5-PB1-Pad19)") (class "Default")
      (node (ref "U5") (pin "19") (pinfunction "PB1_19") (pintype "bidirectional"))
    )
    (net (code "100") (name "unconnected-(U5-PB2-Pad20)") (class "Default")
      (node (ref "U5") (pin "20") (pinfunction "PB2_20") (pintype "bidirectional"))
    )
    (net (code "101") (name "unconnected-(U5-PB8-Pad45)") (class "Default")
      (node (ref "U5") (pin "45") (pinfunction "PB8_45") (pintype "bidirectional"))
    )
    (net (code "102") (name "unconnected-(U5-PB9-Pad46)") (class "Default")
      (node (ref "U5") (pin "46") (pinfunction "PB9_46") (pintype "bidirectional"))
    )
    (net (code "103") (name "unconnected-(U5-PB10-Pad21)") (class "Default")
      (node (ref "U5") (pin "21") (pinfunction "PB10_21") (pintype "bidirectional"))
    )
    (net (code "104") (name "unconnected-(U5-PB11-Pad22)") (class "Default")
      (node (ref "U5") (pin "22") (pinfunction "PB11_22") (pintype "bidirectional"))
    )
    (net (code "105") (name "unconnected-(U5-PB12-Pad25)") (class "Default")
      (node (ref "U5") (pin "25") (pinfunction "PB12_25") (pintype "bidirectional"))
    )
    (net (code "106") (name "unconnected-(U5-PB13-Pad26)") (class "Default")
      (node (ref "U5") (pin "26") (pinfunction "PB13_26") (pintype "bidirectional"))
    )
    (net (code "107") (name "unconnected-(U5-PB14-Pad27)") (class "Default")
      (node (ref "U5") (pin "27") (pinfunction "PB14_27") (pintype "bidirectional"))
    )
    (net (code "108") (name "unconnected-(U5-PB15-Pad28)") (class "Default")
      (node (ref "U5") (pin "28") (pinfunction "PB15_28") (pintype "bidirectional"))
    )
    (net (code "109") (name "unconnected-(U5-VBAT-Pad1)") (class "Default")
      (node (ref "U5") (pin "1") (pinfunction "VBAT_1") (pintype "bidirectional"))
    )
    (net (code "110") (name "unconnected-(X2-Pad5)") (class "Default")
      (node (ref "X2") (pin "5") (pinfunction "5_5") (pintype "passive"))
    )
  )
)
